# murdock_mcu_v4.net
KiCad netlist of a schematic drawn in EAGLE
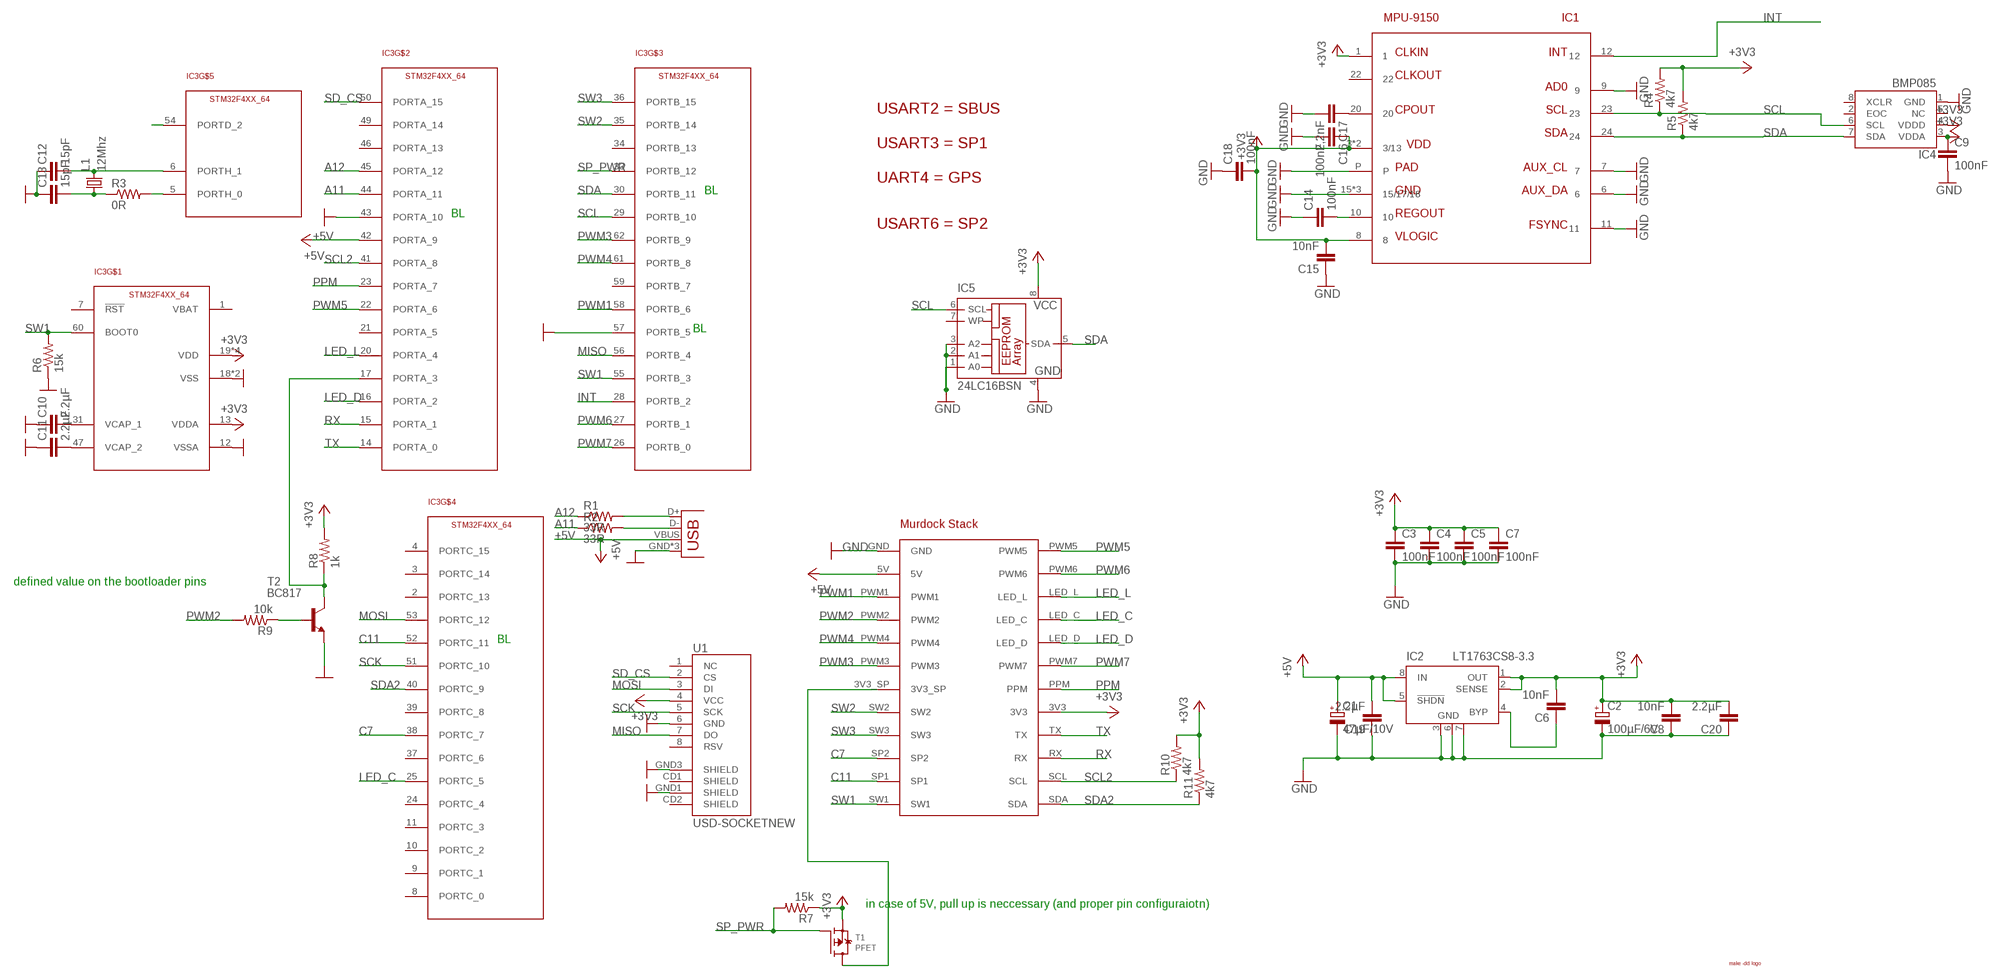
[diagram p0: schematic, sheet 1]

(export (version "E")
  (design (tool "Eeschema 10.0.6"))
  (components
    (comp (ref "C1")
      (value "47µF/10V")
      (footprint "eagle-import:SMC_C")
      (libsource (lib "eagle-import") (part "CPOL-EUSMCC"))
    )
    (comp (ref "C2")
      (value "100µF/6V")
      (footprint "eagle-import:SMC_C")
      (libsource (lib "eagle-import") (part "CPOL-EUSMCC"))
    )
    (comp (ref "C3")
      (value "100nF")
      (footprint "eagle-import:0402-CAP")
      (libsource (lib "eagle-import") (part "SparkFun-Capacitors_CAP0402-CAP"))
    )
    (comp (ref "C4")
      (value "100nF")
      (footprint "eagle-import:0402-CAP")
      (libsource (lib "eagle-import") (part "SparkFun-Capacitors_CAP0402-CAP"))
    )
    (comp (ref "C5")
      (value "100nF")
      (footprint "eagle-import:0402-CAP")
      (libsource (lib "eagle-import") (part "SparkFun-Capacitors_CAP0402-CAP"))
    )
    (comp (ref "C6")
      (value "10nF")
      (footprint "eagle-import:C0402")
      (libsource (lib "eagle-import") (part "C-EUC0402"))
    )
    (comp (ref "C7")
      (value "100nF")
      (footprint "eagle-import:0402-CAP")
      (libsource (lib "eagle-import") (part "SparkFun-Capacitors_CAP0402-CAP"))
    )
    (comp (ref "C8")
      (value "10nF")
      (footprint "eagle-import:C0402")
      (libsource (lib "eagle-import") (part "C-EUC0402"))
    )
    (comp (ref "C9")
      (value "100nF")
      (footprint "eagle-import:0402-CAP")
      (libsource (lib "eagle-import") (part "CAP0402-CAP"))
    )
    (comp (ref "C10")
      (value "2.2µF")
      (footprint "eagle-import:0805")
      (libsource (lib "eagle-import") (part "SparkFun-Capacitors_CAP0805"))
    )
    (comp (ref "C11")
      (value "2.2µF")
      (footprint "eagle-import:0805")
      (libsource (lib "eagle-import") (part "SparkFun-Capacitors_CAP0805"))
    )
    (comp (ref "C12")
      (value "15pF")
      (footprint "eagle-import:0402-CAP")
      (libsource (lib "eagle-import") (part "SparkFun-Capacitors_CAP0402-CAP"))
    )
    (comp (ref "C13")
      (value "15pF")
      (footprint "eagle-import:0402-CAP")
      (libsource (lib "eagle-import") (part "SparkFun-Capacitors_CAP0402-CAP"))
    )
    (comp (ref "C14")
      (value "100nF")
      (footprint "eagle-import:0402-CAP")
      (libsource (lib "eagle-import") (part "CAP0402-CAP"))
    )
    (comp (ref "C15")
      (value "10nF")
      (footprint "eagle-import:0402-CAP")
      (libsource (lib "eagle-import") (part "CAP0402-CAP"))
    )
    (comp (ref "C16")
      (value "100nF")
      (footprint "eagle-import:0402-CAP")
      (libsource (lib "eagle-import") (part "CAP0402-CAP"))
    )
    (comp (ref "C17")
      (value "2,2nF")
      (footprint "eagle-import:0402-CAP")
      (libsource (lib "eagle-import") (part "CAP0402-CAP"))
    )
    (comp (ref "C18")
      (value "100nF")
      (footprint "eagle-import:0402-CAP")
      (libsource (lib "eagle-import") (part "CAP0402-CAP"))
    )
    (comp (ref "C19")
      (value "2.2µF")
      (footprint "eagle-import:0805")
      (libsource (lib "eagle-import") (part "SparkFun-Capacitors_CAP0805"))
    )
    (comp (ref "C20")
      (value "2.2µF")
      (footprint "eagle-import:0805")
      (libsource (lib "eagle-import") (part "SparkFun-Capacitors_CAP0805"))
    )
    (comp (ref "IC1")
      (value "MPU-9150")
      (footprint "eagle-import:QFN24")
      (libsource (lib "eagle-import") (part "MPU-9150"))
    )
    (comp (ref "IC2")
      (value "LT1763CS8-3.3")
      (footprint "eagle-import:SOIC8")
      (libsource (lib "eagle-import") (part "LT1763CS8-3.3"))
    )
    (comp (ref "IC3")
      (value "STM32F4XX_64")
      (footprint "eagle-import:TQFP64")
      (libsource (lib "eagle-import") (part "STM32F4XX_64"))
    )
    (comp (ref "IC4")
      (value "BMP085")
      (footprint "eagle-import:BMP085")
      (libsource (lib "eagle-import") (part "BMP085"))
    )
    (comp (ref "IC5")
      (value "24LC16BSN")
      (footprint "eagle-import:SO-08")
      (fields (field (name "MF") "MICROCHIP") (field (name "MPN") "24LC16B/SN"))
      (libsource (lib "eagle-import") (part "24SNLC16B"))
    )
    (comp (ref "JP1")
      (value "USB-MICROB")
      (footprint "eagle-import:USB-MICROB")
      (libsource (lib "eagle-import") (part "USB-MICROB"))
    )
    (comp (ref "L1")
      (value "12Mhz")
      (footprint "eagle-import:X22")
      (libsource (lib "eagle-import") (part "X22-OSCILLATOR"))
    )
    (comp (ref "R1")
      (value "33R")
      (footprint "eagle-import:0402-RES")
      (libsource (lib "eagle-import") (part "SparkFun-Resistors_RESISTOR0402-RES"))
    )
    (comp (ref "R2")
      (value "33R")
      (footprint "eagle-import:0402-RES")
      (libsource (lib "eagle-import") (part "SparkFun-Resistors_RESISTOR0402-RES"))
    )
    (comp (ref "R3")
      (value "0R")
      (footprint "eagle-import:0402-RES")
      (libsource (lib "eagle-import") (part "SparkFun-Resistors_RESISTOR0402-RES"))
    )
    (comp (ref "R4")
      (value "4k7")
      (footprint "eagle-import:0402-RES")
      (libsource (lib "eagle-import") (part "RESISTOR0402-RES"))
    )
    (comp (ref "R5")
      (value "4k7")
      (footprint "eagle-import:0402-RES")
      (libsource (lib "eagle-import") (part "RESISTOR0402-RES"))
    )
    (comp (ref "R6")
      (value "15k")
      (footprint "eagle-import:0402-RES")
      (libsource (lib "eagle-import") (part "RESISTOR0402-RES"))
    )
    (comp (ref "R7")
      (value "15k")
      (footprint "eagle-import:0402-RES")
      (libsource (lib "eagle-import") (part "SparkFun-Resistors_RESISTOR0402-RES"))
    )
    (comp (ref "R8")
      (value "1k")
      (footprint "eagle-import:0402-RES")
      (libsource (lib "eagle-import") (part "SparkFun-Resistors_RESISTOR0402-RES"))
    )
    (comp (ref "R9")
      (value "10k")
      (footprint "eagle-import:0402-RES")
      (libsource (lib "eagle-import") (part "SparkFun-Resistors_RESISTOR0402-RES"))
    )
    (comp (ref "R10")
      (value "4k7")
      (footprint "eagle-import:0402-RES")
      (libsource (lib "eagle-import") (part "RESISTOR0402-RES"))
    )
    (comp (ref "R11")
      (value "4k7")
      (footprint "eagle-import:0402-RES")
      (libsource (lib "eagle-import") (part "RESISTOR0402-RES"))
    )
    (comp (ref "T1")
      (value "PFET")
      (footprint "eagle-import:SOT23-R")
      (libsource (lib "eagle-import") (part "MOSFET-P"))
    )
    (comp (ref "T2")
      (value "BC817")
      (footprint "eagle-import:SOT23")
      (libsource (lib "eagle-import") (part "BC847"))
    )
    (comp (ref "U$1")
      (value "MAKE-DD_LOGO")
      (footprint "eagle-import:MAKE-DD_LOGO")
      (libsource (lib "eagle-import") (part "MAKE-DD_LOGO"))
    )
    (comp (ref "U1")
      (value "USD-SOCKETNEW")
      (footprint "eagle-import:MICRO-SD-SOCKET-PP")
      (libsource (lib "eagle-import") (part "USD-SOCKETNEW"))
    )
    (comp (ref "X2")
      (value "MURDOCK_STACK")
      (footprint "eagle-import:MURDOCK_STACK")
      (libsource (lib "eagle-import") (part "MURDOCK_STACK"))
    )
  )
  (nets
    (net (code "1") (name "+3V3") (class "Default")
      (node (ref "C15") (pin "2") (pinfunction "2_2") (pintype "passive"))
      (node (ref "C16") (pin "1") (pinfunction "1_1") (pintype "passive"))
      (node (ref "C18") (pin "2") (pinfunction "2_2") (pintype "passive"))
      (node (ref "C2") (pin "+") (pinfunction "+_+") (pintype "passive"))
      (node (ref "C20") (pin "2") (pinfunction "2_2") (pintype "passive"))
      (node (ref "C3") (pin "1") (pinfunction "1_1") (pintype "passive"))
      (node (ref "C4") (pin "1") (pinfunction "1_1") (pintype "passive"))
      (node (ref "C5") (pin "1") (pinfunction "1_1") (pintype "passive"))
      (node (ref "C6") (pin "2") (pinfunction "2_2") (pintype "passive"))
      (node (ref "C7") (pin "1") (pinfunction "1_1") (pintype "passive"))
      (node (ref "C8") (pin "2") (pinfunction "2_2") (pintype "passive"))
      (node (ref "C9") (pin "1") (pinfunction "1_1") (pintype "passive"))
      (node (ref "IC1") (pin "1") (pinfunction "1_1") (pintype "bidirectional"))
      (node (ref "IC1") (pin "13") (pinfunction "3/13_13") (pintype "bidirectional"))
      (node (ref "IC1") (pin "3") (pinfunction "3/13_3") (pintype "bidirectional"))
      (node (ref "IC1") (pin "8") (pinfunction "8_8") (pintype "bidirectional"))
      (node (ref "IC2") (pin "1") (pinfunction "OUT_1") (pintype "passive"))
      (node (ref "IC2") (pin "2") (pinfunction "SENSE_2") (pintype "input"))
      (node (ref "IC3") (pin "13") (pinfunction "VDDA_13") (pintype "bidirectional"))
      (node (ref "IC3") (pin "19") (pinfunction "VDD_19") (pintype "bidirectional"))
      (node (ref "IC3") (pin "32") (pinfunction "VDD_32") (pintype "bidirectional"))
      (node (ref "IC3") (pin "48") (pinfunction "VDD_48") (pintype "bidirectional"))
      (node (ref "IC3") (pin "64") (pinfunction "VDD_64") (pintype "bidirectional"))
      (node (ref "IC4") (pin "3") (pinfunction "VDDA_3") (pintype "power_in"))
      (node (ref "IC4") (pin "4") (pinfunction "VDDD_4") (pintype "power_in"))
      (node (ref "IC5") (pin "8") (pinfunction "VCC_8") (pintype "power_in"))
      (node (ref "R10") (pin "2") (pinfunction "2_2") (pintype "passive"))
      (node (ref "R11") (pin "2") (pinfunction "2_2") (pintype "passive"))
      (node (ref "R4") (pin "2") (pinfunction "2_2") (pintype "passive"))
      (node (ref "R5") (pin "2") (pinfunction "2_2") (pintype "passive"))
      (node (ref "R7") (pin "1") (pinfunction "1_1") (pintype "passive"))
      (node (ref "R8") (pin "2") (pinfunction "2_2") (pintype "passive"))
      (node (ref "T1") (pin "2") (pinfunction "S_2") (pintype "passive"))
      (node (ref "U1") (pin "4") (pinfunction "VCC_4") (pintype "bidirectional"))
      (node (ref "X2") (pin "3V3") (pinfunction "3V3_3V3") (pintype "bidirectional"))
    )
    (net (code "2") (name "+5V") (class "Default")
      (node (ref "C1") (pin "+") (pinfunction "+_+") (pintype "passive"))
      (node (ref "C19") (pin "2") (pinfunction "2_2") (pintype "passive"))
      (node (ref "IC2") (pin "5") (pinfunction "~{SHDN}_5") (pintype "input"))
      (node (ref "IC2") (pin "8") (pinfunction "IN_8") (pintype "input"))
      (node (ref "IC3") (pin "42") (pinfunction "PORTA_9_42") (pintype "bidirectional"))
      (node (ref "JP1") (pin "VBUS") (pinfunction "VBUS_VBUS") (pintype "bidirectional"))
      (node (ref "X2") (pin "5V") (pinfunction "5V_5V") (pintype "bidirectional"))
    )
    (net (code "3") (name "/A11") (class "Default")
      (node (ref "IC3") (pin "44") (pinfunction "PORTA_11_44") (pintype "bidirectional"))
      (node (ref "R2") (pin "1") (pinfunction "1_1") (pintype "passive"))
    )
    (net (code "4") (name "/A12") (class "Default")
      (node (ref "IC3") (pin "45") (pinfunction "PORTA_12_45") (pintype "bidirectional"))
      (node (ref "R1") (pin "1") (pinfunction "1_1") (pintype "passive"))
    )
    (net (code "5") (name "/C7") (class "Default")
      (node (ref "IC3") (pin "38") (pinfunction "PORTC_7_38") (pintype "bidirectional"))
      (node (ref "X2") (pin "SP2") (pinfunction "SP2_SP2") (pintype "bidirectional"))
    )
    (net (code "6") (name "/C11") (class "Default")
      (node (ref "IC3") (pin "52") (pinfunction "PORTC_11_52") (pintype "bidirectional"))
      (node (ref "X2") (pin "SP1") (pinfunction "SP1_SP1") (pintype "bidirectional"))
    )
    (net (code "7") (name "/INT") (class "Default")
      (node (ref "IC1") (pin "12") (pinfunction "12_12") (pintype "bidirectional"))
      (node (ref "IC3") (pin "28") (pinfunction "PORTB_2_28") (pintype "bidirectional"))
    )
    (net (code "8") (name "/LED_C") (class "Default")
      (node (ref "IC3") (pin "25") (pinfunction "PORTC_5_25") (pintype "bidirectional"))
      (node (ref "X2") (pin "LED_C") (pinfunction "LED_C_LED_C") (pintype "bidirectional"))
    )
    (net (code "9") (name "/LED_D") (class "Default")
      (node (ref "IC3") (pin "16") (pinfunction "PORTA_2_16") (pintype "bidirectional"))
      (node (ref "X2") (pin "LED_D") (pinfunction "LED_D_LED_D") (pintype "bidirectional"))
    )
    (net (code "10") (name "/LED_L") (class "Default")
      (node (ref "IC3") (pin "20") (pinfunction "PORTA_4_20") (pintype "bidirectional"))
      (node (ref "X2") (pin "LED_L") (pinfunction "LED_L_LED_L") (pintype "bidirectional"))
    )
    (net (code "11") (name "/MISO") (class "Default")
      (node (ref "IC3") (pin "56") (pinfunction "PORTB_4_56") (pintype "bidirectional"))
      (node (ref "U1") (pin "7") (pinfunction "DO_7") (pintype "bidirectional"))
    )
    (net (code "12") (name "/MOSI") (class "Default")
      (node (ref "IC3") (pin "53") (pinfunction "PORTC_12_53") (pintype "bidirectional"))
      (node (ref "U1") (pin "3") (pinfunction "DI_3") (pintype "bidirectional"))
    )
    (net (code "13") (name "/PPM") (class "Default")
      (node (ref "IC3") (pin "23") (pinfunction "PORTA_7_23") (pintype "bidirectional"))
      (node (ref "X2") (pin "PPM") (pinfunction "PPM_PPM") (pintype "bidirectional"))
    )
    (net (code "14") (name "/PWM1") (class "Default")
      (node (ref "IC3") (pin "58") (pinfunction "PORTB_6_58") (pintype "bidirectional"))
      (node (ref "X2") (pin "PWM1") (pinfunction "PWM1_PWM1") (pintype "bidirectional"))
    )
    (net (code "15") (name "/PWM2") (class "Default")
      (node (ref "R9") (pin "2") (pinfunction "2_2") (pintype "passive"))
      (node (ref "X2") (pin "PWM2") (pinfunction "PWM2_PWM2") (pintype "bidirectional"))
    )
    (net (code "16") (name "/PWM3") (class "Default")
      (node (ref "IC3") (pin "62") (pinfunction "PORTB_9_62") (pintype "bidirectional"))
      (node (ref "X2") (pin "PWM3") (pinfunction "PWM3_PWM3") (pintype "bidirectional"))
    )
    (net (code "17") (name "/PWM4") (class "Default")
      (node (ref "IC3") (pin "61") (pinfunction "PORTB_8_61") (pintype "bidirectional"))
      (node (ref "X2") (pin "PWM4") (pinfunction "PWM4_PWM4") (pintype "bidirectional"))
    )
    (net (code "18") (name "/PWM5") (class "Default")
      (node (ref "IC3") (pin "22") (pinfunction "PORTA_6_22") (pintype "bidirectional"))
      (node (ref "X2") (pin "PWM5") (pinfunction "PWM5_PWM5") (pintype "bidirectional"))
    )
    (net (code "19") (name "/PWM6") (class "Default")
      (node (ref "IC3") (pin "27") (pinfunction "PORTB_1_27") (pintype "bidirectional"))
      (node (ref "X2") (pin "PWM6") (pinfunction "PWM6_PWM6") (pintype "bidirectional"))
    )
    (net (code "20") (name "/PWM7") (class "Default")
      (node (ref "IC3") (pin "26") (pinfunction "PORTB_0_26") (pintype "bidirectional"))
      (node (ref "X2") (pin "PWM7") (pinfunction "PWM7_PWM7") (pintype "bidirectional"))
    )
    (net (code "21") (name "/RX") (class "Default")
      (node (ref "IC3") (pin "15") (pinfunction "PORTA_1_15") (pintype "bidirectional"))
      (node (ref "X2") (pin "RX") (pinfunction "RX_RX") (pintype "bidirectional"))
    )
    (net (code "22") (name "/SCK") (class "Default")
      (node (ref "IC3") (pin "51") (pinfunction "PORTC_10_51") (pintype "bidirectional"))
      (node (ref "U1") (pin "5") (pinfunction "SCK_5") (pintype "bidirectional"))
    )
    (net (code "23") (name "/SCL") (class "Default")
      (node (ref "IC1") (pin "23") (pinfunction "23_23") (pintype "bidirectional"))
      (node (ref "IC3") (pin "29") (pinfunction "PORTB_10_29") (pintype "bidirectional"))
      (node (ref "IC4") (pin "6") (pinfunction "SCL_6") (pintype "input"))
      (node (ref "IC5") (pin "6") (pinfunction "SCL_6") (pintype "input"))
      (node (ref "R4") (pin "1") (pinfunction "1_1") (pintype "passive"))
    )
    (net (code "24") (name "/SCL2") (class "Default")
      (node (ref "IC3") (pin "41") (pinfunction "PORTA_8_41") (pintype "bidirectional"))
      (node (ref "R10") (pin "1") (pinfunction "1_1") (pintype "passive"))
      (node (ref "X2") (pin "SCL") (pinfunction "SCL_SCL") (pintype "bidirectional"))
    )
    (net (code "25") (name "/SDA") (class "Default")
      (node (ref "IC1") (pin "24") (pinfunction "24_24") (pintype "bidirectional"))
      (node (ref "IC3") (pin "30") (pinfunction "PORTB_11_30") (pintype "bidirectional"))
      (node (ref "IC4") (pin "7") (pinfunction "SDA_7") (pintype "bidirectional"))
      (node (ref "IC5") (pin "5") (pinfunction "SDA_5") (pintype "bidirectional"))
      (node (ref "R5") (pin "1") (pinfunction "1_1") (pintype "passive"))
    )
    (net (code "26") (name "/SDA2") (class "Default")
      (node (ref "IC3") (pin "40") (pinfunction "PORTC_9_40") (pintype "bidirectional"))
      (node (ref "R11") (pin "1") (pinfunction "1_1") (pintype "passive"))
      (node (ref "X2") (pin "SDA") (pinfunction "SDA_SDA") (pintype "bidirectional"))
    )
    (net (code "27") (name "/SD_CS") (class "Default")
      (node (ref "IC3") (pin "50") (pinfunction "PORTA_15_50") (pintype "bidirectional"))
      (node (ref "U1") (pin "2") (pinfunction "CS_2") (pintype "bidirectional"))
    )
    (net (code "28") (name "/SP_PWR") (class "Default")
      (node (ref "IC3") (pin "33") (pinfunction "PORTB_12_33") (pintype "bidirectional"))
      (node (ref "R7") (pin "2") (pinfunction "2_2") (pintype "passive"))
      (node (ref "T1") (pin "1") (pinfunction "G_1") (pintype "passive"))
    )
    (net (code "29") (name "/SW1") (class "Default")
      (node (ref "IC3") (pin "55") (pinfunction "PORTB_3_55") (pintype "bidirectional"))
      (node (ref "IC3") (pin "60") (pinfunction "BOOT0_60") (pintype "bidirectional"))
      (node (ref "R6") (pin "2") (pinfunction "2_2") (pintype "passive"))
      (node (ref "X2") (pin "SW1") (pinfunction "SW1_SW1") (pintype "bidirectional"))
    )
    (net (code "30") (name "/SW2") (class "Default")
      (node (ref "IC3") (pin "35") (pinfunction "PORTB_14_35") (pintype "bidirectional"))
      (node (ref "X2") (pin "SW2") (pinfunction "SW2_SW2") (pintype "bidirectional"))
    )
    (net (code "31") (name "/SW3") (class "Default")
      (node (ref "IC3") (pin "36") (pinfunction "PORTB_15_36") (pintype "bidirectional"))
      (node (ref "X2") (pin "SW3") (pinfunction "SW3_SW3") (pintype "bidirectional"))
    )
    (net (code "32") (name "/TX") (class "Default")
      (node (ref "IC3") (pin "14") (pinfunction "PORTA_0_14") (pintype "bidirectional"))
      (node (ref "X2") (pin "TX") (pinfunction "TX_TX") (pintype "bidirectional"))
    )
    (net (code "33") (name "GND") (class "Default")
      (node (ref "C1") (pin "-") (pinfunction "-_-") (pintype "passive"))
      (node (ref "C10") (pin "1") (pinfunction "1_1") (pintype "passive"))
      (node (ref "C11") (pin "1") (pinfunction "1_1") (pintype "passive"))
      (node (ref "C12") (pin "1") (pinfunction "1_1") (pintype "passive"))
      (node (ref "C13") (pin "1") (pinfunction "1_1") (pintype "passive"))
      (node (ref "C14") (pin "1") (pinfunction "1_1") (pintype "passive"))
      (node (ref "C15") (pin "1") (pinfunction "1_1") (pintype "passive"))
      (node (ref "C16") (pin "2") (pinfunction "2_2") (pintype "passive"))
      (node (ref "C17") (pin "2") (pinfunction "2_2") (pintype "passive"))
      (node (ref "C18") (pin "1") (pinfunction "1_1") (pintype "passive"))
      (node (ref "C19") (pin "1") (pinfunction "1_1") (pintype "passive"))
      (node (ref "C2") (pin "-") (pinfunction "-_-") (pintype "passive"))
      (node (ref "C20") (pin "1") (pinfunction "1_1") (pintype "passive"))
      (node (ref "C3") (pin "2") (pinfunction "2_2") (pintype "passive"))
      (node (ref "C4") (pin "2") (pinfunction "2_2") (pintype "passive"))
      (node (ref "C5") (pin "2") (pinfunction "2_2") (pintype "passive"))
      (node (ref "C7") (pin "2") (pinfunction "2_2") (pintype "passive"))
      (node (ref "C8") (pin "1") (pinfunction "1_1") (pintype "passive"))
      (node (ref "C9") (pin "2") (pinfunction "2_2") (pintype "passive"))
      (node (ref "IC1") (pin "11") (pinfunction "11_11") (pintype "bidirectional"))
      (node (ref "IC1") (pin "15") (pinfunction "15/17/18_15") (pintype "bidirectional"))
      (node (ref "IC1") (pin "17") (pinfunction "15/17/18_17") (pintype "bidirectional"))
      (node (ref "IC1") (pin "18") (pinfunction "15/17/18_18") (pintype "bidirectional"))
      (node (ref "IC1") (pin "6") (pinfunction "6_6") (pintype "bidirectional"))
      (node (ref "IC1") (pin "7") (pinfunction "7_7") (pintype "bidirectional"))
      (node (ref "IC1") (pin "9") (pinfunction "9_9") (pintype "bidirectional"))
      (node (ref "IC1") (pin "P") (pinfunction "P_P") (pintype "bidirectional"))
      (node (ref "IC2") (pin "3") (pinfunction "GND_3") (pintype "power_in"))
      (node (ref "IC2") (pin "6") (pinfunction "GND_6") (pintype "power_in"))
      (node (ref "IC2") (pin "7") (pinfunction "GND_7") (pintype "power_in"))
      (node (ref "IC3") (pin "12") (pinfunction "VSSA_12") (pintype "bidirectional"))
      (node (ref "IC3") (pin "18") (pinfunction "VSS_18") (pintype "bidirectional"))
      (node (ref "IC3") (pin "43") (pinfunction "PORTA_10_43") (pintype "bidirectional"))
      (node (ref "IC3") (pin "57") (pinfunction "PORTB_5_57") (pintype "bidirectional"))
      (node (ref "IC3") (pin "63") (pinfunction "VSS_63") (pintype "bidirectional"))
      (node (ref "IC4") (pin "1") (pinfunction "GND_1") (pintype "power_in"))
      (node (ref "IC5") (pin "1") (pinfunction "A0_1") (pintype "input"))
      (node (ref "IC5") (pin "2") (pinfunction "A1_2") (pintype "input"))
      (node (ref "IC5") (pin "3") (pinfunction "A2_3") (pintype "input"))
      (node (ref "IC5") (pin "4") (pinfunction "GND_4") (pintype "power_in"))
      (node (ref "JP1") (pin "GND") (pinfunction "GND_GND") (pintype "bidirectional"))
      (node (ref "JP1") (pin "MT1") (pinfunction "GND_MT1") (pintype "bidirectional"))
      (node (ref "JP1") (pin "MT2") (pinfunction "GND_MT2") (pintype "bidirectional"))
      (node (ref "R6") (pin "1") (pinfunction "1_1") (pintype "passive"))
      (node (ref "T2") (pin "2") (pinfunction "E_2") (pintype "passive"))
      (node (ref "U1") (pin "6") (pinfunction "GND_6") (pintype "bidirectional"))
      (node (ref "U1") (pin "GND1") (pinfunction "SHIELD_GND1") (pintype "bidirectional"))
      (node (ref "U1") (pin "GND3") (pinfunction "SHIELD_GND3") (pintype "bidirectional"))
      (node (ref "X2") (pin "GND") (pinfunction "GND_GND") (pintype "bidirectional"))
    )
    (net (code "34") (name "Net-(C13-Pad2)") (class "Default")
      (node (ref "C13") (pin "2") (pinfunction "2_2") (pintype "passive"))
      (node (ref "L1") (pin "1") (pinfunction "1_1") (pintype "passive"))
      (node (ref "R3") (pin "1") (pinfunction "1_1") (pintype "passive"))
    )
    (net (code "35") (name "Net-(C14-Pad2)") (class "Default")
      (node (ref "C14") (pin "2") (pinfunction "2_2") (pintype "passive"))
      (node (ref "IC1") (pin "10") (pinfunction "10_10") (pintype "bidirectional"))
    )
    (net (code "36") (name "Net-(C17-Pad1)") (class "Default")
      (node (ref "C17") (pin "1") (pinfunction "1_1") (pintype "passive"))
      (node (ref "IC1") (pin "20") (pinfunction "20_20") (pintype "bidirectional"))
    )
    (net (code "37") (name "Net-(IC2-BYP)") (class "Default")
      (node (ref "C6") (pin "1") (pinfunction "1_1") (pintype "passive"))
      (node (ref "IC2") (pin "4") (pinfunction "BYP_4") (pintype "input"))
    )
    (net (code "38") (name "Net-(IC3A-VCAP_1)") (class "Default")
      (node (ref "C10") (pin "2") (pinfunction "2_2") (pintype "passive"))
      (node (ref "IC3") (pin "31") (pinfunction "VCAP_1_31") (pintype "bidirectional"))
    )
    (net (code "39") (name "Net-(IC3A-VCAP_2)") (class "Default")
      (node (ref "C11") (pin "2") (pinfunction "2_2") (pintype "passive"))
      (node (ref "IC3") (pin "47") (pinfunction "VCAP_2_47") (pintype "bidirectional"))
    )
    (net (code "40") (name "Net-(IC3B-PORTA_3)") (class "Default")
      (node (ref "IC3") (pin "17") (pinfunction "PORTA_3_17") (pintype "bidirectional"))
      (node (ref "R8") (pin "1") (pinfunction "1_1") (pintype "passive"))
      (node (ref "T2") (pin "3") (pinfunction "C_3") (pintype "passive"))
    )
    (net (code "41") (name "Net-(IC3E-PORTH_0)") (class "Default")
      (node (ref "IC3") (pin "5") (pinfunction "PORTH_0_5") (pintype "bidirectional"))
      (node (ref "R3") (pin "2") (pinfunction "2_2") (pintype "passive"))
    )
    (net (code "42") (name "Net-(IC3E-PORTH_1)") (class "Default")
      (node (ref "C12") (pin "2") (pinfunction "2_2") (pintype "passive"))
      (node (ref "IC3") (pin "6") (pinfunction "PORTH_1_6") (pintype "bidirectional"))
      (node (ref "L1") (pin "3") (pinfunction "2_3") (pintype "passive"))
    )
    (net (code "43") (name "Net-(JP1-PadD+)") (class "Default")
      (node (ref "JP1") (pin "D+") (pinfunction "D+_D+") (pintype "bidirectional"))
      (node (ref "R1") (pin "2") (pinfunction "2_2") (pintype "passive"))
    )
    (net (code "44") (name "Net-(JP1-PadD-)") (class "Default")
      (node (ref "JP1") (pin "D-") (pinfunction "D-_D-") (pintype "bidirectional"))
      (node (ref "R2") (pin "2") (pinfunction "2_2") (pintype "passive"))
    )
    (net (code "45") (name "Net-(T1-D)") (class "Default")
      (node (ref "T1") (pin "3") (pinfunction "D_3") (pintype "passive"))
      (node (ref "X2") (pin "3V3_SP") (pinfunction "3V3_SP_3V3_SP") (pintype "bidirectional"))
    )
    (net (code "46") (name "Net-(T2-B)") (class "Default")
      (node (ref "R9") (pin "1") (pinfunction "1_1") (pintype "passive"))
      (node (ref "T2") (pin "1") (pinfunction "B_1") (pintype "passive"))
    )
    (net (code "47") (name "unconnected-(IC1-Pad22)") (class "Default")
      (node (ref "IC1") (pin "22") (pinfunction "22_22") (pintype "bidirectional"))
    )
    (net (code "48") (name "unconnected-(IC3A-VBAT-Pad1)") (class "Default")
      (node (ref "IC3") (pin "1") (pinfunction "VBAT_1") (pintype "bidirectional"))
    )
    (net (code "49") (name "unconnected-(IC3A-~{RST}-Pad7)") (class "Default")
      (node (ref "IC3") (pin "7") (pinfunction "~{RST}_7") (pintype "bidirectional"))
    )
    (net (code "50") (name "unconnected-(IC3B-PORTA_5-Pad21)") (class "Default")
      (node (ref "IC3") (pin "21") (pinfunction "PORTA_5_21") (pintype "bidirectional"))
    )
    (net (code "51") (name "unconnected-(IC3B-PORTA_13-Pad46)") (class "Default")
      (node (ref "IC3") (pin "46") (pinfunction "PORTA_13_46") (pintype "bidirectional"))
    )
    (net (code "52") (name "unconnected-(IC3B-PORTA_14-Pad49)") (class "Default")
      (node (ref "IC3") (pin "49") (pinfunction "PORTA_14_49") (pintype "bidirectional"))
    )
    (net (code "53") (name "unconnected-(IC3C-PORTB_7-Pad59)") (class "Default")
      (node (ref "IC3") (pin "59") (pinfunction "PORTB_7_59") (pintype "bidirectional"))
    )
    (net (code "54") (name "unconnected-(IC3C-PORTB_13-Pad34)") (class "Default")
      (node (ref "IC3") (pin "34") (pinfunction "PORTB_13_34") (pintype "bidirectional"))
    )
    (net (code "55") (name "unconnected-(IC3D-PORTC_0-Pad8)") (class "Default")
      (node (ref "IC3") (pin "8") (pinfunction "PORTC_0_8") (pintype "bidirectional"))
    )
    (net (code "56") (name "unconnected-(IC3D-PORTC_1-Pad9)") (class "Default")
      (node (ref "IC3") (pin "9") (pinfunction "PORTC_1_9") (pintype "bidirectional"))
    )
    (net (code "57") (name "unconnected-(IC3D-PORTC_2-Pad10)") (class "Default")
      (node (ref "IC3") (pin "10") (pinfunction "PORTC_2_10") (pintype "bidirectional"))
    )
    (net (code "58") (name "unconnected-(IC3D-PORTC_3-Pad11)") (class "Default")
      (node (ref "IC3") (pin "11") (pinfunction "PORTC_3_11") (pintype "bidirectional"))
    )
    (net (code "59") (name "unconnected-(IC3D-PORTC_4-Pad24)") (class "Default")
      (node (ref "IC3") (pin "24") (pinfunction "PORTC_4_24") (pintype "bidirectional"))
    )
    (net (code "60") (name "unconnected-(IC3D-PORTC_6-Pad37)") (class "Default")
      (node (ref "IC3") (pin "37") (pinfunction "PORTC_6_37") (pintype "bidirectional"))
    )
    (net (code "61") (name "unconnected-(IC3D-PORTC_8-Pad39)") (class "Default")
      (node (ref "IC3") (pin "39") (pinfunction "PORTC_8_39") (pintype "bidirectional"))
    )
    (net (code "62") (name "unconnected-(IC3D-PORTC_13-Pad2)") (class "Default")
      (node (ref "IC3") (pin "2") (pinfunction "PORTC_13_2") (pintype "bidirectional"))
    )
    (net (code "63") (name "unconnected-(IC3D-PORTC_14-Pad3)") (class "Default")
      (node (ref "IC3") (pin "3") (pinfunction "PORTC_14_3") (pintype "bidirectional"))
    )
    (net (code "64") (name "unconnected-(IC3D-PORTC_15-Pad4)") (class "Default")
      (node (ref "IC3") (pin "4") (pinfunction "PORTC_15_4") (pintype "bidirectional"))
    )
    (net (code "65") (name "unconnected-(IC3E-PORTD_2-Pad54)") (class "Default")
      (node (ref "IC3") (pin "54") (pinfunction "PORTD_2_54") (pintype "bidirectional"))
    )
    (net (code "66") (name "unconnected-(IC4-EOC-Pad2)") (class "Default")
      (node (ref "IC4") (pin "2") (pinfunction "EOC_2") (pintype "output"))
    )
    (net (code "67") (name "unconnected-(IC4-NC-Pad5)") (class "Default")
      (node (ref "IC4") (pin "5") (pinfunction "NC_5") (pintype "bidirectional"))
    )
    (net (code "68") (name "unconnected-(IC4-XCLR-Pad8)") (class "Default")
      (node (ref "IC4") (pin "8") (pinfunction "XCLR_8") (pintype "input"))
    )
    (net (code "69") (name "unconnected-(IC5-WP-Pad7)") (class "Default")
      (node (ref "IC5") (pin "7") (pinfunction "WP_7") (pintype "input"))
    )
    (net (code "70") (name "unconnected-(U1-NC-Pad1)") (class "Default")
      (node (ref "U1") (pin "1") (pinfunction "NC_1") (pintype "bidirectional"))
    )
    (net (code "71") (name "unconnected-(U1-RSV-Pad8)") (class "Default")
      (node (ref "U1") (pin "8") (pinfunction "RSV_8") (pintype "bidirectional"))
    )
    (net (code "72") (name "unconnected-(U1-SHIELD-PadCD1)") (class "Default")
      (node (ref "U1") (pin "CD1") (pinfunction "SHIELD_CD1") (pintype "bidirectional"))
    )
    (net (code "73") (name "unconnected-(U1-SHIELD-PadCD2)") (class "Default")
      (node (ref "U1") (pin "CD2") (pinfunction "SHIELD_CD2") (pintype "bidirectional"))
    )
  )
)
